# Power_and_Crystal.net
KiCad netlist of a schematic drawn in Altium Designer
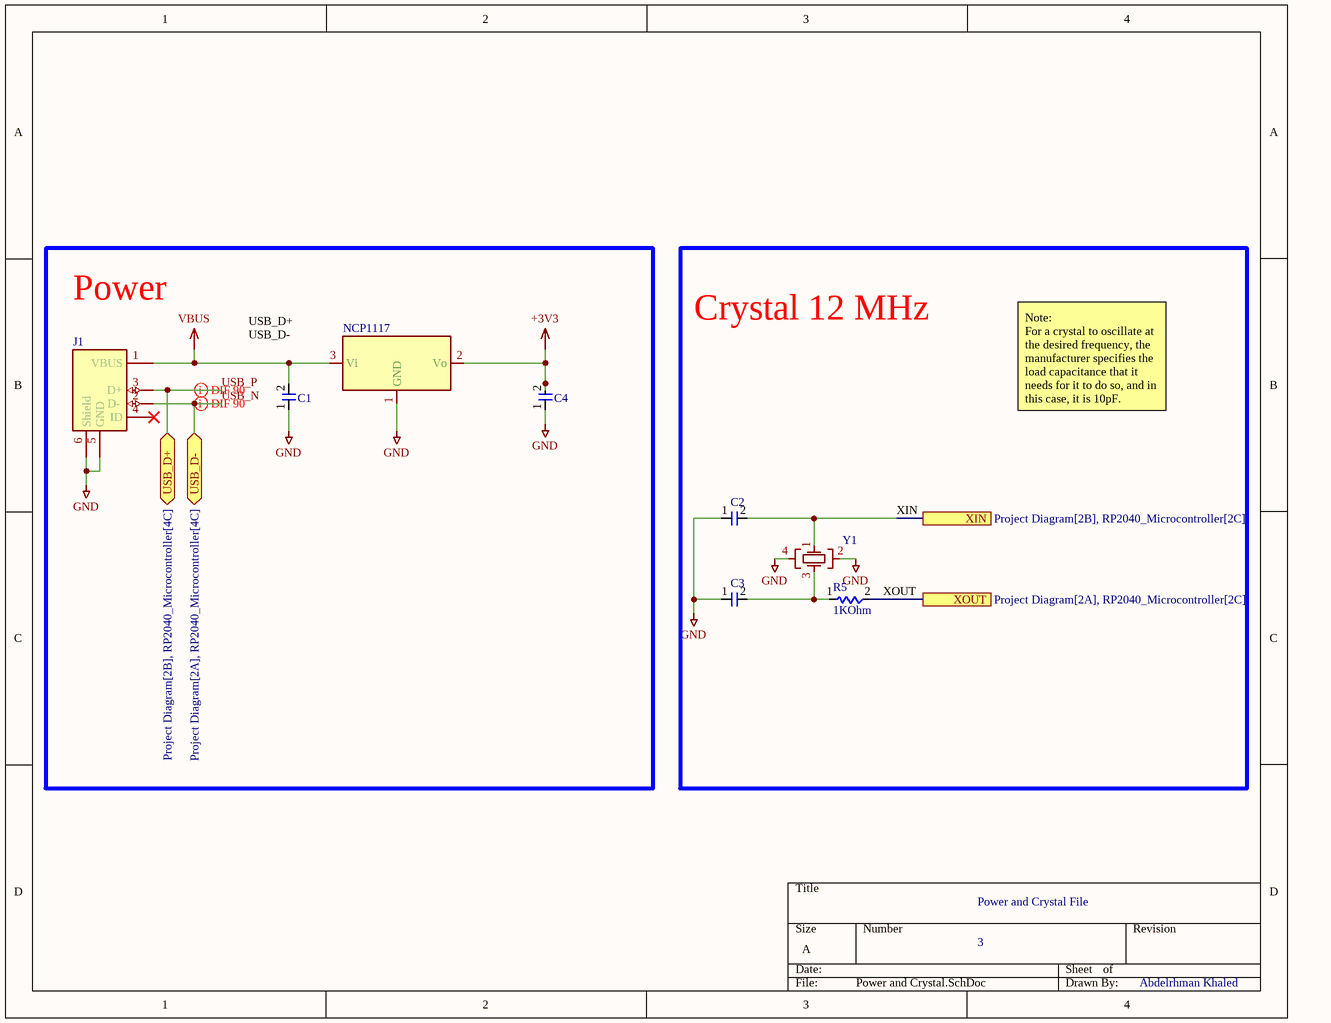
[diagram p0: Power and Crystal.SchDoc]

(export (version "E")
  (design (tool "Eeschema 10.0.6"))
  (components
    (comp (ref "C1")
      (value "10UF Capacitor")
      (footprint "CL21A106KOQNNNE - duplicate")
      (description "10 µF ±10% 16V Ceramic Capacitor X5R 0805 (2012 Metric)")
      (fields (field (name "PART NUMBER") "CL21A106KOQNNNE"))
      (libsource (lib "RP2040_Integrated_Library") (part "CL21A106KOQNNNE"))
    )
    (comp (ref "C2")
      (value "CAP CER 15PF 50V")
      (footprint "CAP CER 15PF 50V")
      (description "15 pF ±5% 50V Ceramic Capacitor C0G, NP0 0805 (2012 Metric)")
      (fields (field (name "PART NUMBER") "CC0805JRNPO9BN150"))
      (libsource (lib "RP2040_Integrated_Library") (part "CAP CER 15PF 50V"))
    )
    (comp (ref "C3")
      (value "CAP CER 15PF 50V")
      (footprint "CAP CER 15PF 50V")
      (description "15 pF ±5% 50V Ceramic Capacitor C0G, NP0 0805 (2012 Metric)")
      (fields (field (name "PART NUMBER") "CC0805JRNPO9BN150"))
      (libsource (lib "RP2040_Integrated_Library") (part "CAP CER 15PF 50V"))
    )
    (comp (ref "C4")
      (value "10UF Capacitor")
      (footprint "CL21A106KOQNNNE - duplicate")
      (description "10 µF ±10% 16V Ceramic Capacitor X5R 0805 (2012 Metric)")
      (fields (field (name "PART NUMBER") "CL21A106KOQNNNE"))
      (libsource (lib "RP2040_Integrated_Library") (part "CL21A106KOQNNNE"))
    )
    (comp (ref "J1")
      (value "USB_B Micro")
      (footprint "USB_B Micro")
      (description "Conn Data USB Micro B w/Flange SMT Bottom Mnt LF ¦ Molex Incorporated 47346-0001")
      (fields (field (name "PART NUMBER") "47346-0001"))
      (libsource (lib "RP2040_Integrated_Library") (part "USB_B Micro"))
    )
    (comp (ref "NCP1117")
      (value "IC REG LINEAR 3.3V 1A SOT223")
      (footprint "NCP1117LPST33T3G")
      (description "Linear Voltage Regulator IC Positive Fixed 1 Output 1A SOT-223")
      (fields (field (name "PART NUMBER") "NCP1117LPST33T3GOSTR-ND"))
      (libsource (lib "RP2040_Integrated_Library") (part "NCP1117LPST33T3G"))
    )
    (comp (ref "R5")
      (value "1KOhm")
      (footprint "RC1206FR-078K06L")
      (description "8.06 kOhms ±1% 0.25W, 1/4W Chip Resistor 1206 (3216 Metric) Moisture Resistant Thick Film")
      (fields (field (name "PART NUMBER") "RC1206FR-078K06L"))
      (libsource (lib "RP2040_Integrated_Library") (part "RC1206FR-078K06L"))
    )
    (comp (ref "Y1")
      (value "Crystal 12 MHz")
      (footprint "Crystal 12 MHz")
      (description "12 MHz ±30ppm Crystal 18pF 150 Ohms 4-SMD, No Lead")
      (fields (field (name "PART NUMBER") "403C35D12M00000"))
      (libsource (lib "RP2040_Integrated_Library") (part "Crystal 12 MHz"))
    )
  )
  (nets
    (net (code "1") (name "+3V3") (class "Default")
      (node (ref "C4") (pin "2") (pinfunction "Pin_2_2") (pintype "passive"))
      (node (ref "NCP1117") (pin "2") (pinfunction "Vo_2") (pintype "power_in"))
    )
    (net (code "2") (name "/USB_D+") (class "Default")
      (node (ref "J1") (pin "3") (pinfunction "D+_3") (pintype "bidirectional"))
    )
    (net (code "3") (name "/USB_D-") (class "Default")
      (node (ref "J1") (pin "2") (pinfunction "D-_2") (pintype "bidirectional"))
    )
    (net (code "4") (name "/XIN") (class "Default")
      (node (ref "C2") (pin "2") (pinfunction "Pin_2_2") (pintype "passive"))
      (node (ref "Y1") (pin "1") (pinfunction "6_1") (pintype "passive"))
    )
    (net (code "5") (name "/XOUT") (class "Default")
      (node (ref "R5") (pin "2") (pinfunction "pin_2_2") (pintype "passive"))
    )
    (net (code "6") (name "GND") (class "Default")
      (node (ref "C1") (pin "1") (pinfunction "Pin_1_1") (pintype "passive"))
      (node (ref "C2") (pin "1") (pinfunction "Pin_1_1") (pintype "passive"))
      (node (ref "C3") (pin "1") (pinfunction "Pin_1_1") (pintype "passive"))
      (node (ref "C4") (pin "1") (pinfunction "Pin_1_1") (pintype "passive"))
      (node (ref "J1") (pin "5") (pinfunction "GND_5") (pintype "power_in"))
      (node (ref "J1") (pin "6") (pinfunction "Shield_6") (pintype "power_in"))
      (node (ref "NCP1117") (pin "1") (pinfunction "GND_1") (pintype "power_in"))
      (node (ref "Y1") (pin "2") (pinfunction "2_2") (pintype "passive"))
      (node (ref "Y1") (pin "4") (pinfunction "6_4") (pintype "passive"))
    )
    (net (code "7") (name "Net-(C3-Pin_2)") (class "Default")
      (node (ref "C3") (pin "2") (pinfunction "Pin_2_2") (pintype "passive"))
      (node (ref "R5") (pin "1") (pinfunction "Pin_1_1") (pintype "passive"))
      (node (ref "Y1") (pin "3") (pinfunction "3_3") (pintype "passive"))
    )
    (net (code "8") (name "VBUS") (class "Default")
      (node (ref "C1") (pin "2") (pinfunction "Pin_2_2") (pintype "passive"))
      (node (ref "J1") (pin "1") (pinfunction "VBUS_1") (pintype "power_in"))
      (node (ref "NCP1117") (pin "3") (pinfunction "Vi_3") (pintype "power_in"))
    )
    (net (code "9") (name "unconnected-(J1-ID-Pad4)") (class "Default")
      (node (ref "J1") (pin "4") (pinfunction "ID_4") (pintype "passive+no_connect"))
    )
  )
)
